# 16_Vibrationdriver_PCA9685.net
KiCad netlist of a schematic drawn in EAGLE
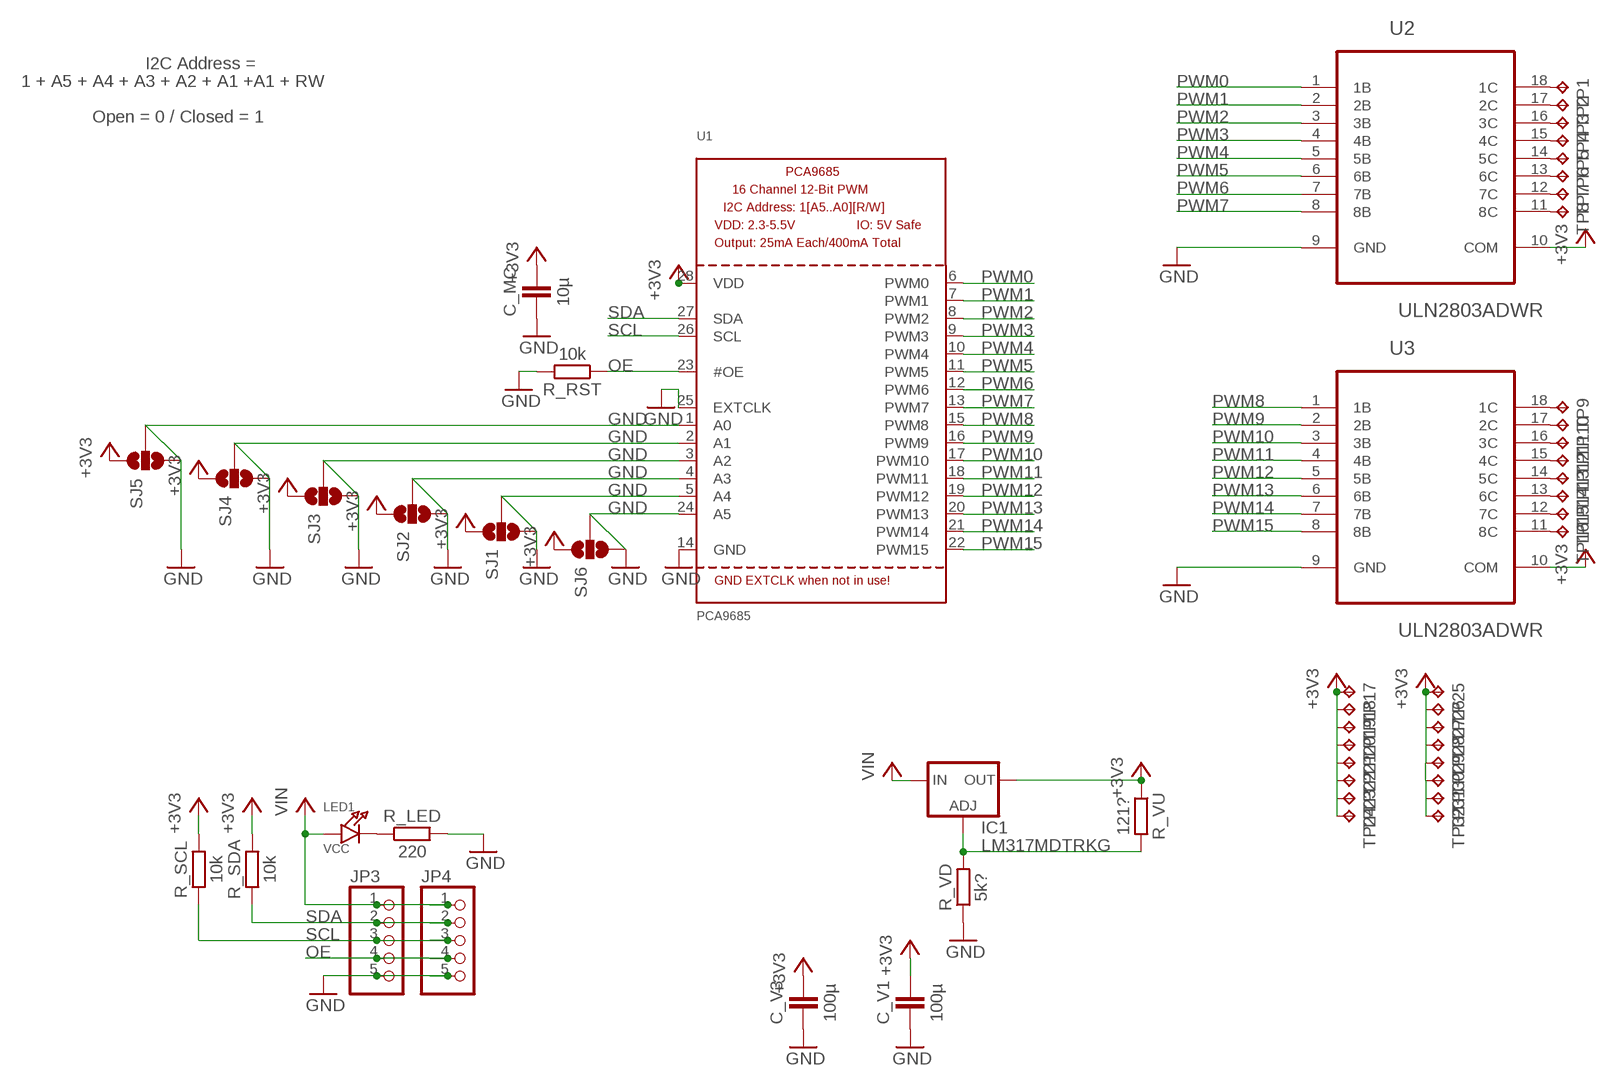
[diagram p0: schematic, sheet 1]

(export (version "E")
  (design (tool "Eeschema 10.0.6"))
  (components
    (comp (ref "C_MC")
      (value "10µ")
      (footprint "eagle-import:603")
      (libsource (lib "eagle-import") (part "CAPACITOR"))
    )
    (comp (ref "C_V1")
      (value "100µ")
      (footprint "eagle-import:1206")
      (libsource (lib "eagle-import") (part "CAPACITOR1206"))
    )
    (comp (ref "C_V3")
      (value "100µ")
      (footprint "eagle-import:1206")
      (libsource (lib "eagle-import") (part "CAPACITOR1206"))
    )
    (comp (ref "IC1")
      (value "LM317MDTRKG")
      (footprint "eagle-import:DPACK")
      (libsource (lib "eagle-import") (part "LM317?MDTRKG"))
    )
    (comp (ref "JP3")
      (value "PINHD-1X5")
      (footprint "eagle-import:1X05")
      (libsource (lib "eagle-import") (part "PINHD-1X5"))
    )
    (comp (ref "JP4")
      (value "PINHD-1X5")
      (footprint "eagle-import:1X05")
      (libsource (lib "eagle-import") (part "PINHD-1X5"))
    )
    (comp (ref "LED1")
      (value "VCC")
      (footprint "eagle-import:CHIPLED_0805")
      (libsource (lib "eagle-import") (part "LED0805"))
    )
    (comp (ref "R_LED")
      (value "220")
      (footprint "eagle-import:603")
      (libsource (lib "eagle-import") (part "RESISTOR0603"))
    )
    (comp (ref "R_RST")
      (value "10k")
      (footprint "eagle-import:603")
      (libsource (lib "eagle-import") (part "RESISTOR0603"))
    )
    (comp (ref "R_SCL")
      (value "10k")
      (footprint "eagle-import:603")
      (libsource (lib "eagle-import") (part "RESISTOR0603"))
    )
    (comp (ref "R_SDA")
      (value "10k")
      (footprint "eagle-import:603")
      (libsource (lib "eagle-import") (part "RESISTOR0603"))
    )
    (comp (ref "R_VD")
      (value "5k?")
      (footprint "eagle-import:603")
      (libsource (lib "eagle-import") (part "RESISTOR0603"))
    )
    (comp (ref "R_VU")
      (value "121?")
      (footprint "eagle-import:603")
      (libsource (lib "eagle-import") (part "RESISTOR0603"))
    )
    (comp (ref "SJ1")
      (value "SOLDERJUMPER_2WAYPASTE2&3")
      (footprint "eagle-import:SJ_3_PASTE2&3")
      (libsource (lib "eagle-import") (part "SOLDERJUMPER_2WAYPASTE2&3"))
    )
    (comp (ref "SJ2")
      (value "SOLDERJUMPER_2WAYPASTE2&3")
      (footprint "eagle-import:SJ_3_PASTE2&3")
      (libsource (lib "eagle-import") (part "SOLDERJUMPER_2WAYPASTE2&3"))
    )
    (comp (ref "SJ3")
      (value "SOLDERJUMPER_2WAYPASTE2&3")
      (footprint "eagle-import:SJ_3_PASTE2&3")
      (libsource (lib "eagle-import") (part "SOLDERJUMPER_2WAYPASTE2&3"))
    )
    (comp (ref "SJ4")
      (value "SOLDERJUMPER_2WAYPASTE2&3")
      (footprint "eagle-import:SJ_3_PASTE2&3")
      (libsource (lib "eagle-import") (part "SOLDERJUMPER_2WAYPASTE2&3"))
    )
    (comp (ref "SJ5")
      (value "SOLDERJUMPER_2WAYPASTE2&3")
      (footprint "eagle-import:SJ_3_PASTE2&3")
      (libsource (lib "eagle-import") (part "SOLDERJUMPER_2WAYPASTE2&3"))
    )
    (comp (ref "SJ6")
      (value "SOLDERJUMPER_2WAYPASTE2&3")
      (footprint "eagle-import:SJ_3_PASTE2&3")
      (libsource (lib "eagle-import") (part "SOLDERJUMPER_2WAYPASTE2&3"))
    )
    (comp (ref "TP1")
      (value "TPTP16SQ")
      (footprint "eagle-import:TP16SQ")
      (libsource (lib "eagle-import") (part "TPTP16SQ"))
    )
    (comp (ref "TP2")
      (value "TPTP16SQ")
      (footprint "eagle-import:TP16SQ")
      (libsource (lib "eagle-import") (part "TPTP16SQ"))
    )
    (comp (ref "TP3")
      (value "TPTP16SQ")
      (footprint "eagle-import:TP16SQ")
      (libsource (lib "eagle-import") (part "TPTP16SQ"))
    )
    (comp (ref "TP4")
      (value "TPTP16SQ")
      (footprint "eagle-import:TP16SQ")
      (libsource (lib "eagle-import") (part "TPTP16SQ"))
    )
    (comp (ref "TP5")
      (value "TPTP16SQ")
      (footprint "eagle-import:TP16SQ")
      (libsource (lib "eagle-import") (part "TPTP16SQ"))
    )
    (comp (ref "TP6")
      (value "TPTP16SQ")
      (footprint "eagle-import:TP16SQ")
      (libsource (lib "eagle-import") (part "TPTP16SQ"))
    )
    (comp (ref "TP7")
      (value "TPTP16SQ")
      (footprint "eagle-import:TP16SQ")
      (libsource (lib "eagle-import") (part "TPTP16SQ"))
    )
    (comp (ref "TP8")
      (value "TPTP16SQ")
      (footprint "eagle-import:TP16SQ")
      (libsource (lib "eagle-import") (part "TPTP16SQ"))
    )
    (comp (ref "TP9")
      (value "TPTP16SQ")
      (footprint "eagle-import:TP16SQ")
      (libsource (lib "eagle-import") (part "TPTP16SQ"))
    )
    (comp (ref "TP10")
      (value "TPTP16SQ")
      (footprint "eagle-import:TP16SQ")
      (libsource (lib "eagle-import") (part "TPTP16SQ"))
    )
    (comp (ref "TP11")
      (value "TPTP16SQ")
      (footprint "eagle-import:TP16SQ")
      (libsource (lib "eagle-import") (part "TPTP16SQ"))
    )
    (comp (ref "TP12")
      (value "TPTP16SQ")
      (footprint "eagle-import:TP16SQ")
      (libsource (lib "eagle-import") (part "TPTP16SQ"))
    )
    (comp (ref "TP13")
      (value "TPTP16SQ")
      (footprint "eagle-import:TP16SQ")
      (libsource (lib "eagle-import") (part "TPTP16SQ"))
    )
    (comp (ref "TP14")
      (value "TPTP16SQ")
      (footprint "eagle-import:TP16SQ")
      (libsource (lib "eagle-import") (part "TPTP16SQ"))
    )
    (comp (ref "TP15")
      (value "TPTP16SQ")
      (footprint "eagle-import:TP16SQ")
      (libsource (lib "eagle-import") (part "TPTP16SQ"))
    )
    (comp (ref "TP16")
      (value "TPTP16SQ")
      (footprint "eagle-import:TP16SQ")
      (libsource (lib "eagle-import") (part "TPTP16SQ"))
    )
    (comp (ref "TP17")
      (value "TPTP16SQ")
      (footprint "eagle-import:TP16SQ")
      (libsource (lib "eagle-import") (part "TPTP16SQ"))
    )
    (comp (ref "TP18")
      (value "TPTP16SQ")
      (footprint "eagle-import:TP16SQ")
      (libsource (lib "eagle-import") (part "TPTP16SQ"))
    )
    (comp (ref "TP19")
      (value "TPTP16SQ")
      (footprint "eagle-import:TP16SQ")
      (libsource (lib "eagle-import") (part "TPTP16SQ"))
    )
    (comp (ref "TP20")
      (value "TPTP16SQ")
      (footprint "eagle-import:TP16SQ")
      (libsource (lib "eagle-import") (part "TPTP16SQ"))
    )
    (comp (ref "TP21")
      (value "TPTP16SQ")
      (footprint "eagle-import:TP16SQ")
      (libsource (lib "eagle-import") (part "TPTP16SQ"))
    )
    (comp (ref "TP22")
      (value "TPTP16SQ")
      (footprint "eagle-import:TP16SQ")
      (libsource (lib "eagle-import") (part "TPTP16SQ"))
    )
    (comp (ref "TP23")
      (value "TPTP16SQ")
      (footprint "eagle-import:TP16SQ")
      (libsource (lib "eagle-import") (part "TPTP16SQ"))
    )
    (comp (ref "TP24")
      (value "TPTP16SQ")
      (footprint "eagle-import:TP16SQ")
      (libsource (lib "eagle-import") (part "TPTP16SQ"))
    )
    (comp (ref "TP25")
      (value "TPTP16SQ")
      (footprint "eagle-import:TP16SQ")
      (libsource (lib "eagle-import") (part "TPTP16SQ"))
    )
    (comp (ref "TP26")
      (value "TPTP16SQ")
      (footprint "eagle-import:TP16SQ")
      (libsource (lib "eagle-import") (part "TPTP16SQ"))
    )
    (comp (ref "TP27")
      (value "TPTP16SQ")
      (footprint "eagle-import:TP16SQ")
      (libsource (lib "eagle-import") (part "TPTP16SQ"))
    )
    (comp (ref "TP28")
      (value "TPTP16SQ")
      (footprint "eagle-import:TP16SQ")
      (libsource (lib "eagle-import") (part "TPTP16SQ"))
    )
    (comp (ref "TP29")
      (value "TPTP16SQ")
      (footprint "eagle-import:TP16SQ")
      (libsource (lib "eagle-import") (part "TPTP16SQ"))
    )
    (comp (ref "TP30")
      (value "TPTP16SQ")
      (footprint "eagle-import:TP16SQ")
      (libsource (lib "eagle-import") (part "TPTP16SQ"))
    )
    (comp (ref "TP31")
      (value "TPTP16SQ")
      (footprint "eagle-import:TP16SQ")
      (libsource (lib "eagle-import") (part "TPTP16SQ"))
    )
    (comp (ref "TP32")
      (value "TPTP16SQ")
      (footprint "eagle-import:TP16SQ")
      (libsource (lib "eagle-import") (part "TPTP16SQ"))
    )
    (comp (ref "U1")
      (value "PCA9685")
      (footprint "eagle-import:TSSOP28")
      (libsource (lib "eagle-import") (part "PCA9685"))
    )
    (comp (ref "U2")
      (value "ULN2803ADWR")
      (footprint "eagle-import:SOIC127P1030X265-18N")
      (libsource (lib "eagle-import") (part "ULN2803ADWR"))
    )
    (comp (ref "U3")
      (value "ULN2803ADWR")
      (footprint "eagle-import:SOIC127P1030X265-18N")
      (libsource (lib "eagle-import") (part "ULN2803ADWR"))
    )
  )
  (nets
    (net (code "1") (name "+3V3") (class "Default")
      (node (ref "C_MC") (pin "2") (pinfunction "2_2") (pintype "passive"))
      (node (ref "C_V1") (pin "2") (pinfunction "2_2") (pintype "passive"))
      (node (ref "C_V3") (pin "2") (pinfunction "2_2") (pintype "passive"))
      (node (ref "IC1") (pin "4") (pinfunction "OUT_4") (pintype "passive"))
      (node (ref "R_SCL") (pin "2") (pinfunction "2_2") (pintype "passive"))
      (node (ref "R_SDA") (pin "2") (pinfunction "2_2") (pintype "passive"))
      (node (ref "R_VU") (pin "1") (pinfunction "1_1") (pintype "passive"))
      (node (ref "SJ1") (pin "1") (pinfunction "1_1") (pintype "passive"))
      (node (ref "SJ2") (pin "1") (pinfunction "1_1") (pintype "passive"))
      (node (ref "SJ3") (pin "1") (pinfunction "1_1") (pintype "passive"))
      (node (ref "SJ4") (pin "1") (pinfunction "1_1") (pintype "passive"))
      (node (ref "SJ5") (pin "1") (pinfunction "1_1") (pintype "passive"))
      (node (ref "SJ6") (pin "1") (pinfunction "1_1") (pintype "passive"))
      (node (ref "TP17") (pin "TP") (pinfunction "TP_TP") (pintype "input"))
      (node (ref "TP18") (pin "TP") (pinfunction "TP_TP") (pintype "input"))
      (node (ref "TP19") (pin "TP") (pinfunction "TP_TP") (pintype "input"))
      (node (ref "TP20") (pin "TP") (pinfunction "TP_TP") (pintype "input"))
      (node (ref "TP21") (pin "TP") (pinfunction "TP_TP") (pintype "input"))
      (node (ref "TP22") (pin "TP") (pinfunction "TP_TP") (pintype "input"))
      (node (ref "TP23") (pin "TP") (pinfunction "TP_TP") (pintype "input"))
      (node (ref "TP24") (pin "TP") (pinfunction "TP_TP") (pintype "input"))
      (node (ref "TP25") (pin "TP") (pinfunction "TP_TP") (pintype "input"))
      (node (ref "TP26") (pin "TP") (pinfunction "TP_TP") (pintype "input"))
      (node (ref "TP27") (pin "TP") (pinfunction "TP_TP") (pintype "input"))
      (node (ref "TP28") (pin "TP") (pinfunction "TP_TP") (pintype "input"))
      (node (ref "TP29") (pin "TP") (pinfunction "TP_TP") (pintype "input"))
      (node (ref "TP30") (pin "TP") (pinfunction "TP_TP") (pintype "input"))
      (node (ref "TP31") (pin "TP") (pinfunction "TP_TP") (pintype "input"))
      (node (ref "TP32") (pin "TP") (pinfunction "TP_TP") (pintype "input"))
      (node (ref "U1") (pin "28") (pinfunction "VDD_28") (pintype "power_in"))
      (node (ref "U2") (pin "10") (pinfunction "COM_10") (pintype "output"))
      (node (ref "U3") (pin "10") (pinfunction "COM_10") (pintype "output"))
    )
    (net (code "2") (name "/OE") (class "Default")
      (node (ref "JP3") (pin "4") (pinfunction "4_4") (pintype "passive"))
      (node (ref "JP4") (pin "4") (pinfunction "4_4") (pintype "passive"))
      (node (ref "R_RST") (pin "1") (pinfunction "1_1") (pintype "passive"))
      (node (ref "U1") (pin "23") (pinfunction "#OE_23") (pintype "input"))
    )
    (net (code "3") (name "/PWM0") (class "Default")
      (node (ref "U1") (pin "6") (pinfunction "PWM0_6") (pintype "output"))
      (node (ref "U2") (pin "1") (pinfunction "1B_1") (pintype "input"))
    )
    (net (code "4") (name "/PWM1") (class "Default")
      (node (ref "U1") (pin "7") (pinfunction "PWM1_7") (pintype "output"))
      (node (ref "U2") (pin "2") (pinfunction "2B_2") (pintype "input"))
    )
    (net (code "5") (name "/PWM2") (class "Default")
      (node (ref "U1") (pin "8") (pinfunction "PWM2_8") (pintype "output"))
      (node (ref "U2") (pin "3") (pinfunction "3B_3") (pintype "input"))
    )
    (net (code "6") (name "/PWM3") (class "Default")
      (node (ref "U1") (pin "9") (pinfunction "PWM3_9") (pintype "output"))
      (node (ref "U2") (pin "4") (pinfunction "4B_4") (pintype "input"))
    )
    (net (code "7") (name "/PWM4") (class "Default")
      (node (ref "U1") (pin "10") (pinfunction "PWM4_10") (pintype "output"))
      (node (ref "U2") (pin "5") (pinfunction "5B_5") (pintype "input"))
    )
    (net (code "8") (name "/PWM5") (class "Default")
      (node (ref "U1") (pin "11") (pinfunction "PWM5_11") (pintype "output"))
      (node (ref "U2") (pin "6") (pinfunction "6B_6") (pintype "input"))
    )
    (net (code "9") (name "/PWM6") (class "Default")
      (node (ref "U1") (pin "12") (pinfunction "PWM6_12") (pintype "output"))
      (node (ref "U2") (pin "7") (pinfunction "7B_7") (pintype "input"))
    )
    (net (code "10") (name "/PWM7") (class "Default")
      (node (ref "U1") (pin "13") (pinfunction "PWM7_13") (pintype "output"))
      (node (ref "U2") (pin "8") (pinfunction "8B_8") (pintype "input"))
    )
    (net (code "11") (name "/PWM8") (class "Default")
      (node (ref "U1") (pin "15") (pinfunction "PWM8_15") (pintype "output"))
      (node (ref "U3") (pin "1") (pinfunction "1B_1") (pintype "input"))
    )
    (net (code "12") (name "/PWM9") (class "Default")
      (node (ref "U1") (pin "16") (pinfunction "PWM9_16") (pintype "output"))
      (node (ref "U3") (pin "2") (pinfunction "2B_2") (pintype "input"))
    )
    (net (code "13") (name "/PWM10") (class "Default")
      (node (ref "U1") (pin "17") (pinfunction "PWM10_17") (pintype "output"))
      (node (ref "U3") (pin "3") (pinfunction "3B_3") (pintype "input"))
    )
    (net (code "14") (name "/PWM11") (class "Default")
      (node (ref "U1") (pin "18") (pinfunction "PWM11_18") (pintype "output"))
      (node (ref "U3") (pin "4") (pinfunction "4B_4") (pintype "input"))
    )
    (net (code "15") (name "/PWM12") (class "Default")
      (node (ref "U1") (pin "19") (pinfunction "PWM12_19") (pintype "output"))
      (node (ref "U3") (pin "5") (pinfunction "5B_5") (pintype "input"))
    )
    (net (code "16") (name "/PWM13") (class "Default")
      (node (ref "U1") (pin "20") (pinfunction "PWM13_20") (pintype "output"))
      (node (ref "U3") (pin "6") (pinfunction "6B_6") (pintype "input"))
    )
    (net (code "17") (name "/PWM14") (class "Default")
      (node (ref "U1") (pin "21") (pinfunction "PWM14_21") (pintype "output"))
      (node (ref "U3") (pin "7") (pinfunction "7B_7") (pintype "input"))
    )
    (net (code "18") (name "/PWM15") (class "Default")
      (node (ref "U1") (pin "22") (pinfunction "PWM15_22") (pintype "output"))
      (node (ref "U3") (pin "8") (pinfunction "8B_8") (pintype "input"))
    )
    (net (code "19") (name "/SCL") (class "Default")
      (node (ref "JP3") (pin "3") (pinfunction "3_3") (pintype "passive"))
      (node (ref "JP4") (pin "3") (pinfunction "3_3") (pintype "passive"))
      (node (ref "R_SCL") (pin "1") (pinfunction "1_1") (pintype "passive"))
      (node (ref "U1") (pin "26") (pinfunction "SCL_26") (pintype "bidirectional"))
    )
    (net (code "20") (name "/SDA") (class "Default")
      (node (ref "JP3") (pin "2") (pinfunction "2_2") (pintype "passive"))
      (node (ref "JP4") (pin "2") (pinfunction "2_2") (pintype "passive"))
      (node (ref "R_SDA") (pin "1") (pinfunction "1_1") (pintype "passive"))
      (node (ref "U1") (pin "27") (pinfunction "SDA_27") (pintype "bidirectional"))
    )
    (net (code "21") (name "GND") (class "Default")
      (node (ref "C_MC") (pin "1") (pinfunction "1_1") (pintype "passive"))
      (node (ref "C_V1") (pin "1") (pinfunction "1_1") (pintype "passive"))
      (node (ref "C_V3") (pin "1") (pinfunction "1_1") (pintype "passive"))
      (node (ref "JP3") (pin "5") (pinfunction "5_5") (pintype "passive"))
      (node (ref "JP4") (pin "5") (pinfunction "5_5") (pintype "passive"))
      (node (ref "R_LED") (pin "2") (pinfunction "2_2") (pintype "passive"))
      (node (ref "R_RST") (pin "2") (pinfunction "2_2") (pintype "passive"))
      (node (ref "R_VD") (pin "1") (pinfunction "1_1") (pintype "passive"))
      (node (ref "SJ1") (pin "2") (pinfunction "2_2") (pintype "passive"))
      (node (ref "SJ1") (pin "3") (pinfunction "3_3") (pintype "passive"))
      (node (ref "SJ2") (pin "2") (pinfunction "2_2") (pintype "passive"))
      (node (ref "SJ2") (pin "3") (pinfunction "3_3") (pintype "passive"))
      (node (ref "SJ3") (pin "2") (pinfunction "2_2") (pintype "passive"))
      (node (ref "SJ3") (pin "3") (pinfunction "3_3") (pintype "passive"))
      (node (ref "SJ4") (pin "2") (pinfunction "2_2") (pintype "passive"))
      (node (ref "SJ4") (pin "3") (pinfunction "3_3") (pintype "passive"))
      (node (ref "SJ5") (pin "2") (pinfunction "2_2") (pintype "passive"))
      (node (ref "SJ5") (pin "3") (pinfunction "3_3") (pintype "passive"))
      (node (ref "SJ6") (pin "2") (pinfunction "2_2") (pintype "passive"))
      (node (ref "SJ6") (pin "3") (pinfunction "3_3") (pintype "passive"))
      (node (ref "U1") (pin "1") (pinfunction "A0_1") (pintype "bidirectional"))
      (node (ref "U1") (pin "14") (pinfunction "GND_14") (pintype "power_in"))
      (node (ref "U1") (pin "2") (pinfunction "A1_2") (pintype "bidirectional"))
      (node (ref "U1") (pin "24") (pinfunction "A5_24") (pintype "bidirectional"))
      (node (ref "U1") (pin "25") (pinfunction "EXTCLK_25") (pintype "input"))
      (node (ref "U1") (pin "3") (pinfunction "A2_3") (pintype "bidirectional"))
      (node (ref "U1") (pin "4") (pinfunction "A3_4") (pintype "bidirectional"))
      (node (ref "U1") (pin "5") (pinfunction "A4_5") (pintype "bidirectional"))
      (node (ref "U2") (pin "9") (pinfunction "GND_9") (pintype "passive"))
      (node (ref "U3") (pin "9") (pinfunction "GND_9") (pintype "passive"))
    )
    (net (code "22") (name "Net-(IC1-ADJ)") (class "Default")
      (node (ref "IC1") (pin "1") (pinfunction "ADJ_1") (pintype "input"))
      (node (ref "R_VD") (pin "2") (pinfunction "2_2") (pintype "passive"))
      (node (ref "R_VU") (pin "2") (pinfunction "2_2") (pintype "passive"))
    )
    (net (code "23") (name "Net-(LED1-PadC)") (class "Default")
      (node (ref "LED1") (pin "C") (pinfunction "C_C") (pintype "passive"))
      (node (ref "R_LED") (pin "1") (pinfunction "1_1") (pintype "passive"))
    )
    (net (code "24") (name "Net-(U2-1C)") (class "Default")
      (node (ref "TP1") (pin "TP") (pinfunction "TP_TP") (pintype "input"))
      (node (ref "U2") (pin "18") (pinfunction "1C_18") (pintype "output"))
    )
    (net (code "25") (name "Net-(U2-2C)") (class "Default")
      (node (ref "TP2") (pin "TP") (pinfunction "TP_TP") (pintype "input"))
      (node (ref "U2") (pin "17") (pinfunction "2C_17") (pintype "output"))
    )
    (net (code "26") (name "Net-(U2-3C)") (class "Default")
      (node (ref "TP3") (pin "TP") (pinfunction "TP_TP") (pintype "input"))
      (node (ref "U2") (pin "16") (pinfunction "3C_16") (pintype "output"))
    )
    (net (code "27") (name "Net-(U2-4C)") (class "Default")
      (node (ref "TP4") (pin "TP") (pinfunction "TP_TP") (pintype "input"))
      (node (ref "U2") (pin "15") (pinfunction "4C_15") (pintype "output"))
    )
    (net (code "28") (name "Net-(U2-5C)") (class "Default")
      (node (ref "TP5") (pin "TP") (pinfunction "TP_TP") (pintype "input"))
      (node (ref "U2") (pin "14") (pinfunction "5C_14") (pintype "output"))
    )
    (net (code "29") (name "Net-(U2-6C)") (class "Default")
      (node (ref "TP6") (pin "TP") (pinfunction "TP_TP") (pintype "input"))
      (node (ref "U2") (pin "13") (pinfunction "6C_13") (pintype "output"))
    )
    (net (code "30") (name "Net-(U2-7C)") (class "Default")
      (node (ref "TP7") (pin "TP") (pinfunction "TP_TP") (pintype "input"))
      (node (ref "U2") (pin "12") (pinfunction "7C_12") (pintype "output"))
    )
    (net (code "31") (name "Net-(U2-8C)") (class "Default")
      (node (ref "TP8") (pin "TP") (pinfunction "TP_TP") (pintype "input"))
      (node (ref "U2") (pin "11") (pinfunction "8C_11") (pintype "output"))
    )
    (net (code "32") (name "Net-(U3-1C)") (class "Default")
      (node (ref "TP9") (pin "TP") (pinfunction "TP_TP") (pintype "input"))
      (node (ref "U3") (pin "18") (pinfunction "1C_18") (pintype "output"))
    )
    (net (code "33") (name "Net-(U3-2C)") (class "Default")
      (node (ref "TP10") (pin "TP") (pinfunction "TP_TP") (pintype "input"))
      (node (ref "U3") (pin "17") (pinfunction "2C_17") (pintype "output"))
    )
    (net (code "34") (name "Net-(U3-3C)") (class "Default")
      (node (ref "TP11") (pin "TP") (pinfunction "TP_TP") (pintype "input"))
      (node (ref "U3") (pin "16") (pinfunction "3C_16") (pintype "output"))
    )
    (net (code "35") (name "Net-(U3-4C)") (class "Default")
      (node (ref "TP12") (pin "TP") (pinfunction "TP_TP") (pintype "input"))
      (node (ref "U3") (pin "15") (pinfunction "4C_15") (pintype "output"))
    )
    (net (code "36") (name "Net-(U3-5C)") (class "Default")
      (node (ref "TP13") (pin "TP") (pinfunction "TP_TP") (pintype "input"))
      (node (ref "U3") (pin "14") (pinfunction "5C_14") (pintype "output"))
    )
    (net (code "37") (name "Net-(U3-6C)") (class "Default")
      (node (ref "TP14") (pin "TP") (pinfunction "TP_TP") (pintype "input"))
      (node (ref "U3") (pin "13") (pinfunction "6C_13") (pintype "output"))
    )
    (net (code "38") (name "Net-(U3-7C)") (class "Default")
      (node (ref "TP15") (pin "TP") (pinfunction "TP_TP") (pintype "input"))
      (node (ref "U3") (pin "12") (pinfunction "7C_12") (pintype "output"))
    )
    (net (code "39") (name "Net-(U3-8C)") (class "Default")
      (node (ref "TP16") (pin "TP") (pinfunction "TP_TP") (pintype "input"))
      (node (ref "U3") (pin "11") (pinfunction "8C_11") (pintype "output"))
    )
    (net (code "40") (name "VIN") (class "Default")
      (node (ref "IC1") (pin "3") (pinfunction "IN_3") (pintype "input"))
      (node (ref "JP3") (pin "1") (pinfunction "1_1") (pintype "passive"))
      (node (ref "JP4") (pin "1") (pinfunction "1_1") (pintype "passive"))
      (node (ref "LED1") (pin "A") (pinfunction "A_A") (pintype "passive"))
    )
  )
)
